# ChillmonBoard.net
KiCad netlist of a schematic drawn in EAGLE
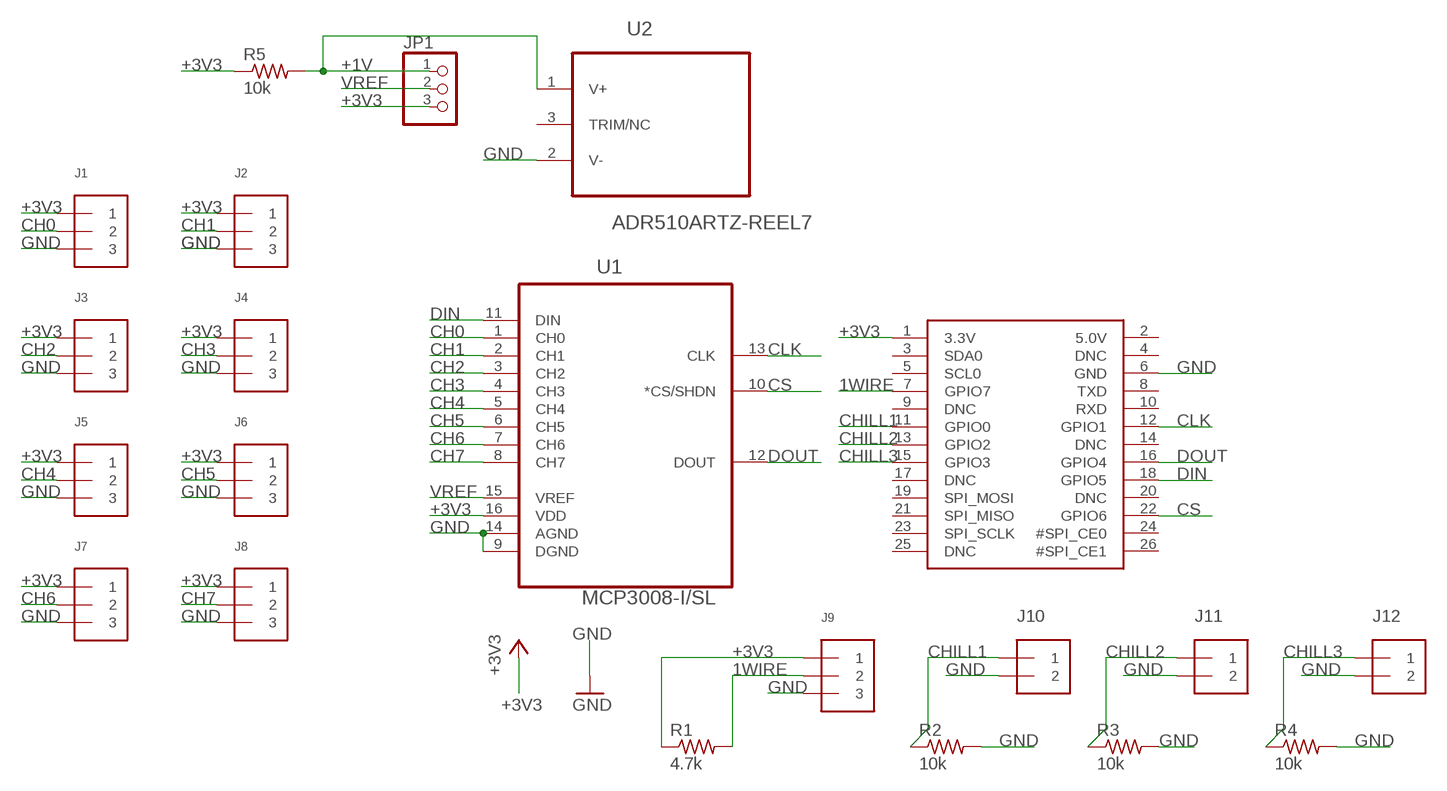
[diagram p0: schematic, sheet 1]

(export (version "E")
  (design (tool "Eeschema 10.0.6"))
  (components
    (comp (ref "J1")
      (value "TERMBLOCK_1X3")
      (footprint "eagle-import:TERMBLOCK_1X3-3.5MM")
      (libsource (lib "eagle-import") (part "TERMBLOCK_1X3"))
    )
    (comp (ref "J2")
      (value "TERMBLOCK_1X3")
      (footprint "eagle-import:TERMBLOCK_1X3-3.5MM")
      (libsource (lib "eagle-import") (part "TERMBLOCK_1X3"))
    )
    (comp (ref "J3")
      (value "TERMBLOCK_1X3")
      (footprint "eagle-import:TERMBLOCK_1X3-3.5MM")
      (libsource (lib "eagle-import") (part "TERMBLOCK_1X3"))
    )
    (comp (ref "J4")
      (value "TERMBLOCK_1X3")
      (footprint "eagle-import:TERMBLOCK_1X3-3.5MM")
      (libsource (lib "eagle-import") (part "TERMBLOCK_1X3"))
    )
    (comp (ref "J5")
      (value "TERMBLOCK_1X3")
      (footprint "eagle-import:TERMBLOCK_1X3-3.5MM")
      (libsource (lib "eagle-import") (part "TERMBLOCK_1X3"))
    )
    (comp (ref "J6")
      (value "TERMBLOCK_1X3")
      (footprint "eagle-import:TERMBLOCK_1X3-3.5MM")
      (libsource (lib "eagle-import") (part "TERMBLOCK_1X3"))
    )
    (comp (ref "J7")
      (value "TERMBLOCK_1X3")
      (footprint "eagle-import:TERMBLOCK_1X3-3.5MM")
      (libsource (lib "eagle-import") (part "TERMBLOCK_1X3"))
    )
    (comp (ref "J8")
      (value "TERMBLOCK_1X3")
      (footprint "eagle-import:TERMBLOCK_1X3-3.5MM")
      (libsource (lib "eagle-import") (part "TERMBLOCK_1X3"))
    )
    (comp (ref "J9")
      (value "TERMBLOCK_1X3")
      (footprint "eagle-import:TERMBLOCK_1X3-3.5MM")
      (libsource (lib "eagle-import") (part "TERMBLOCK_1X3"))
    )
    (comp (ref "J10")
      (value "1X2-3.5MM")
      (footprint "eagle-import:1X2-3.5MM")
      (libsource (lib "eagle-import") (part "1X2-3.5MM"))
    )
    (comp (ref "J11")
      (value "1X2-3.5MM")
      (footprint "eagle-import:1X2-3.5MM")
      (libsource (lib "eagle-import") (part "1X2-3.5MM"))
    )
    (comp (ref "J12")
      (value "1X2-3.5MM")
      (footprint "eagle-import:1X2-3.5MM")
      (libsource (lib "eagle-import") (part "1X2-3.5MM"))
    )
    (comp (ref "JP1")
      (value "PINHD-1X3")
      (footprint "eagle-import:1X03")
      (libsource (lib "eagle-import") (part "PINHD-1X3"))
    )
    (comp (ref "R1")
      (value "4.7k")
      (footprint "eagle-import:R0805")
      (libsource (lib "eagle-import") (part "R-US_R0805"))
    )
    (comp (ref "R2")
      (value "10k")
      (footprint "eagle-import:R0805")
      (libsource (lib "eagle-import") (part "R-US_R0805"))
    )
    (comp (ref "R3")
      (value "10k")
      (footprint "eagle-import:R0805")
      (libsource (lib "eagle-import") (part "R-US_R0805"))
    )
    (comp (ref "R4")
      (value "10k")
      (footprint "eagle-import:R0805")
      (libsource (lib "eagle-import") (part "R-US_R0805"))
    )
    (comp (ref "R5")
      (value "10k")
      (footprint "eagle-import:R0805")
      (libsource (lib "eagle-import") (part "R-US_R0805"))
    )
    (comp (ref "U$1")
      (value "RASPBERRYPI_BB")
      (footprint "eagle-import:RASBERRYPI_SHIELD")
      (libsource (lib "eagle-import") (part "RASPBERRYPI_BB"))
    )
    (comp (ref "U1")
      (value "MCP3008-I/SL")
      (footprint "eagle-import:SOIC127P600X175-16N")
      (libsource (lib "eagle-import") (part "MCP3008-I/SL"))
    )
    (comp (ref "U2")
      (value "ADR510ARTZ-REEL7")
      (footprint "eagle-import:SOT95P237X112-3N")
      (libsource (lib "eagle-import") (part "ADR510ARTZ-REEL7"))
    )
  )
  (nets
    (net (code "1") (name "+3V3") (class "Default")
      (node (ref "J1") (pin "1") (pinfunction "1_1") (pintype "passive"))
      (node (ref "J2") (pin "1") (pinfunction "1_1") (pintype "passive"))
      (node (ref "J3") (pin "1") (pinfunction "1_1") (pintype "passive"))
      (node (ref "J4") (pin "1") (pinfunction "1_1") (pintype "passive"))
      (node (ref "J5") (pin "1") (pinfunction "1_1") (pintype "passive"))
      (node (ref "J6") (pin "1") (pinfunction "1_1") (pintype "passive"))
      (node (ref "J7") (pin "1") (pinfunction "1_1") (pintype "passive"))
      (node (ref "J8") (pin "1") (pinfunction "1_1") (pintype "passive"))
      (node (ref "J9") (pin "1") (pinfunction "1_1") (pintype "passive"))
      (node (ref "JP1") (pin "3") (pinfunction "3_3") (pintype "passive"))
      (node (ref "R1") (pin "1") (pinfunction "1_1") (pintype "passive"))
      (node (ref "R5") (pin "1") (pinfunction "1_1") (pintype "passive"))
      (node (ref "U$1") (pin "1") (pinfunction "3.3V_1") (pintype "power_in"))
      (node (ref "U1") (pin "16") (pinfunction "VDD_16") (pintype "power_in"))
    )
    (net (code "2") (name "/+1V") (class "Default")
      (node (ref "JP1") (pin "1") (pinfunction "1_1") (pintype "passive"))
      (node (ref "R5") (pin "2") (pinfunction "2_2") (pintype "passive"))
      (node (ref "U2") (pin "1") (pinfunction "V+_1") (pintype "power_in"))
    )
    (net (code "3") (name "/1WIRE") (class "Default")
      (node (ref "J9") (pin "2") (pinfunction "2_2") (pintype "passive"))
      (node (ref "R1") (pin "2") (pinfunction "2_2") (pintype "passive"))
      (node (ref "U$1") (pin "7") (pinfunction "GPIO7_7") (pintype "bidirectional"))
    )
    (net (code "4") (name "/5.0V") (class "Default")
      (node (ref "U$1") (pin "2") (pinfunction "5.0V_2") (pintype "power_in"))
    )
    (net (code "5") (name "/CH0") (class "Default")
      (node (ref "J1") (pin "2") (pinfunction "2_2") (pintype "passive"))
      (node (ref "U1") (pin "1") (pinfunction "CH0_1") (pintype "input"))
    )
    (net (code "6") (name "/CH1") (class "Default")
      (node (ref "J2") (pin "2") (pinfunction "2_2") (pintype "passive"))
      (node (ref "U1") (pin "2") (pinfunction "CH1_2") (pintype "input"))
    )
    (net (code "7") (name "/CH2") (class "Default")
      (node (ref "J3") (pin "2") (pinfunction "2_2") (pintype "passive"))
      (node (ref "U1") (pin "3") (pinfunction "CH2_3") (pintype "input"))
    )
    (net (code "8") (name "/CH3") (class "Default")
      (node (ref "J4") (pin "2") (pinfunction "2_2") (pintype "passive"))
      (node (ref "U1") (pin "4") (pinfunction "CH3_4") (pintype "input"))
    )
    (net (code "9") (name "/CH4") (class "Default")
      (node (ref "J5") (pin "2") (pinfunction "2_2") (pintype "passive"))
      (node (ref "U1") (pin "5") (pinfunction "CH4_5") (pintype "input"))
    )
    (net (code "10") (name "/CH5") (class "Default")
      (node (ref "J6") (pin "2") (pinfunction "2_2") (pintype "passive"))
      (node (ref "U1") (pin "6") (pinfunction "CH5_6") (pintype "input"))
    )
    (net (code "11") (name "/CH6") (class "Default")
      (node (ref "J7") (pin "2") (pinfunction "2_2") (pintype "passive"))
      (node (ref "U1") (pin "7") (pinfunction "CH6_7") (pintype "input"))
    )
    (net (code "12") (name "/CH7") (class "Default")
      (node (ref "J8") (pin "2") (pinfunction "2_2") (pintype "passive"))
      (node (ref "U1") (pin "8") (pinfunction "CH7_8") (pintype "input"))
    )
    (net (code "13") (name "/CHILL1") (class "Default")
      (node (ref "J10") (pin "1") (pinfunction "1_1") (pintype "passive"))
      (node (ref "R2") (pin "1") (pinfunction "1_1") (pintype "passive"))
      (node (ref "U$1") (pin "11") (pinfunction "GPIO0_11") (pintype "bidirectional"))
    )
    (net (code "14") (name "/CHILL2") (class "Default")
      (node (ref "J11") (pin "1") (pinfunction "1_1") (pintype "passive"))
      (node (ref "R3") (pin "1") (pinfunction "1_1") (pintype "passive"))
      (node (ref "U$1") (pin "13") (pinfunction "GPIO2_13") (pintype "bidirectional"))
    )
    (net (code "15") (name "/CHILL3") (class "Default")
      (node (ref "J12") (pin "1") (pinfunction "1_1") (pintype "passive"))
      (node (ref "R4") (pin "1") (pinfunction "1_1") (pintype "passive"))
      (node (ref "U$1") (pin "15") (pinfunction "GPIO3_15") (pintype "bidirectional"))
    )
    (net (code "16") (name "/CLK") (class "Default")
      (node (ref "U$1") (pin "12") (pinfunction "GPIO1_12") (pintype "bidirectional"))
      (node (ref "U1") (pin "13") (pinfunction "CLK_13") (pintype "input"))
    )
    (net (code "17") (name "/CS") (class "Default")
      (node (ref "U$1") (pin "22") (pinfunction "GPIO6_22") (pintype "bidirectional"))
      (node (ref "U1") (pin "10") (pinfunction "*CS/SHDN_10") (pintype "input"))
    )
    (net (code "18") (name "/DIN") (class "Default")
      (node (ref "U$1") (pin "18") (pinfunction "GPIO5_18") (pintype "bidirectional"))
      (node (ref "U1") (pin "11") (pinfunction "DIN_11") (pintype "input"))
    )
    (net (code "19") (name "/DOUT") (class "Default")
      (node (ref "U$1") (pin "16") (pinfunction "GPIO4_16") (pintype "bidirectional"))
      (node (ref "U1") (pin "12") (pinfunction "DOUT_12") (pintype "output"))
    )
    (net (code "20") (name "/VREF") (class "Default")
      (node (ref "JP1") (pin "2") (pinfunction "2_2") (pintype "passive"))
      (node (ref "U1") (pin "15") (pinfunction "VREF_15") (pintype "input"))
    )
    (net (code "21") (name "GND") (class "Default")
      (node (ref "J1") (pin "3") (pinfunction "3_3") (pintype "passive"))
      (node (ref "J10") (pin "2") (pinfunction "2_2") (pintype "passive"))
      (node (ref "J11") (pin "2") (pinfunction "2_2") (pintype "passive"))
      (node (ref "J12") (pin "2") (pinfunction "2_2") (pintype "passive"))
      (node (ref "J2") (pin "3") (pinfunction "3_3") (pintype "passive"))
      (node (ref "J3") (pin "3") (pinfunction "3_3") (pintype "passive"))
      (node (ref "J4") (pin "3") (pinfunction "3_3") (pintype "passive"))
      (node (ref "J5") (pin "3") (pinfunction "3_3") (pintype "passive"))
      (node (ref "J6") (pin "3") (pinfunction "3_3") (pintype "passive"))
      (node (ref "J7") (pin "3") (pinfunction "3_3") (pintype "passive"))
      (node (ref "J8") (pin "3") (pinfunction "3_3") (pintype "passive"))
      (node (ref "J9") (pin "3") (pinfunction "3_3") (pintype "passive"))
      (node (ref "R2") (pin "2") (pinfunction "2_2") (pintype "passive"))
      (node (ref "R3") (pin "2") (pinfunction "2_2") (pintype "passive"))
      (node (ref "R4") (pin "2") (pinfunction "2_2") (pintype "passive"))
      (node (ref "U$1") (pin "6") (pinfunction "GND_6") (pintype "power_in"))
      (node (ref "U1") (pin "14") (pinfunction "AGND_14") (pintype "passive"))
      (node (ref "U1") (pin "9") (pinfunction "DGND_9") (pintype "passive"))
      (node (ref "U2") (pin "2") (pinfunction "V-_2") (pintype "power_in"))
    )
    (net (code "22") (name "unconnected-(U$1-#SPI_CE0-Pad24)") (class "Default")
      (node (ref "U$1") (pin "24") (pinfunction "#SPI_CE0_24") (pintype "output"))
    )
    (net (code "23") (name "unconnected-(U$1-#SPI_CE1-Pad26)") (class "Default")
      (node (ref "U$1") (pin "26") (pinfunction "#SPI_CE1_26") (pintype "output"))
    )
    (net (code "24") (name "unconnected-(U$1-DNC-Pad4)") (class "Default")
      (node (ref "U$1") (pin "4") (pinfunction "DNC_4") (pintype "no_connect"))
    )
    (net (code "25") (name "unconnected-(U$1-DNC-Pad9)") (class "Default")
      (node (ref "U$1") (pin "9") (pinfunction "DNC_9") (pintype "no_connect"))
    )
    (net (code "26") (name "unconnected-(U$1-DNC-Pad14)") (class "Default")
      (node (ref "U$1") (pin "14") (pinfunction "DNC_14") (pintype "no_connect"))
    )
    (net (code "27") (name "unconnected-(U$1-DNC-Pad17)") (class "Default")
      (node (ref "U$1") (pin "17") (pinfunction "DNC_17") (pintype "no_connect"))
    )
    (net (code "28") (name "unconnected-(U$1-DNC-Pad20)") (class "Default")
      (node (ref "U$1") (pin "20") (pinfunction "DNC_20") (pintype "no_connect"))
    )
    (net (code "29") (name "unconnected-(U$1-DNC-Pad25)") (class "Default")
      (node (ref "U$1") (pin "25") (pinfunction "DNC_25") (pintype "no_connect"))
    )
    (net (code "30") (name "unconnected-(U$1-RXD-Pad10)") (class "Default")
      (node (ref "U$1") (pin "10") (pinfunction "RXD_10") (pintype "input"))
    )
    (net (code "31") (name "unconnected-(U$1-SCL0-Pad5)") (class "Default")
      (node (ref "U$1") (pin "5") (pinfunction "SCL0_5") (pintype "output"))
    )
    (net (code "32") (name "unconnected-(U$1-SDA0-Pad3)") (class "Default")
      (node (ref "U$1") (pin "3") (pinfunction "SDA0_3") (pintype "bidirectional"))
    )
    (net (code "33") (name "unconnected-(U$1-SPI_MISO-Pad21)") (class "Default")
      (node (ref "U$1") (pin "21") (pinfunction "SPI_MISO_21") (pintype "input"))
    )
    (net (code "34") (name "unconnected-(U$1-SPI_MOSI-Pad19)") (class "Default")
      (node (ref "U$1") (pin "19") (pinfunction "SPI_MOSI_19") (pintype "output"))
    )
    (net (code "35") (name "unconnected-(U$1-SPI_SCLK-Pad23)") (class "Default")
      (node (ref "U$1") (pin "23") (pinfunction "SPI_SCLK_23") (pintype "output"))
    )
    (net (code "36") (name "unconnected-(U$1-TXD-Pad8)") (class "Default")
      (node (ref "U$1") (pin "8") (pinfunction "TXD_8") (pintype "output"))
    )
    (net (code "37") (name "unconnected-(U2-TRIM{slash}NC-Pad3)") (class "Default")
      (node (ref "U2") (pin "3") (pinfunction "TRIM/NC_3") (pintype "passive"))
    )
  )
)
